# Modulo_Generico.net
KiCad netlist of a schematic drawn in Altium Designer
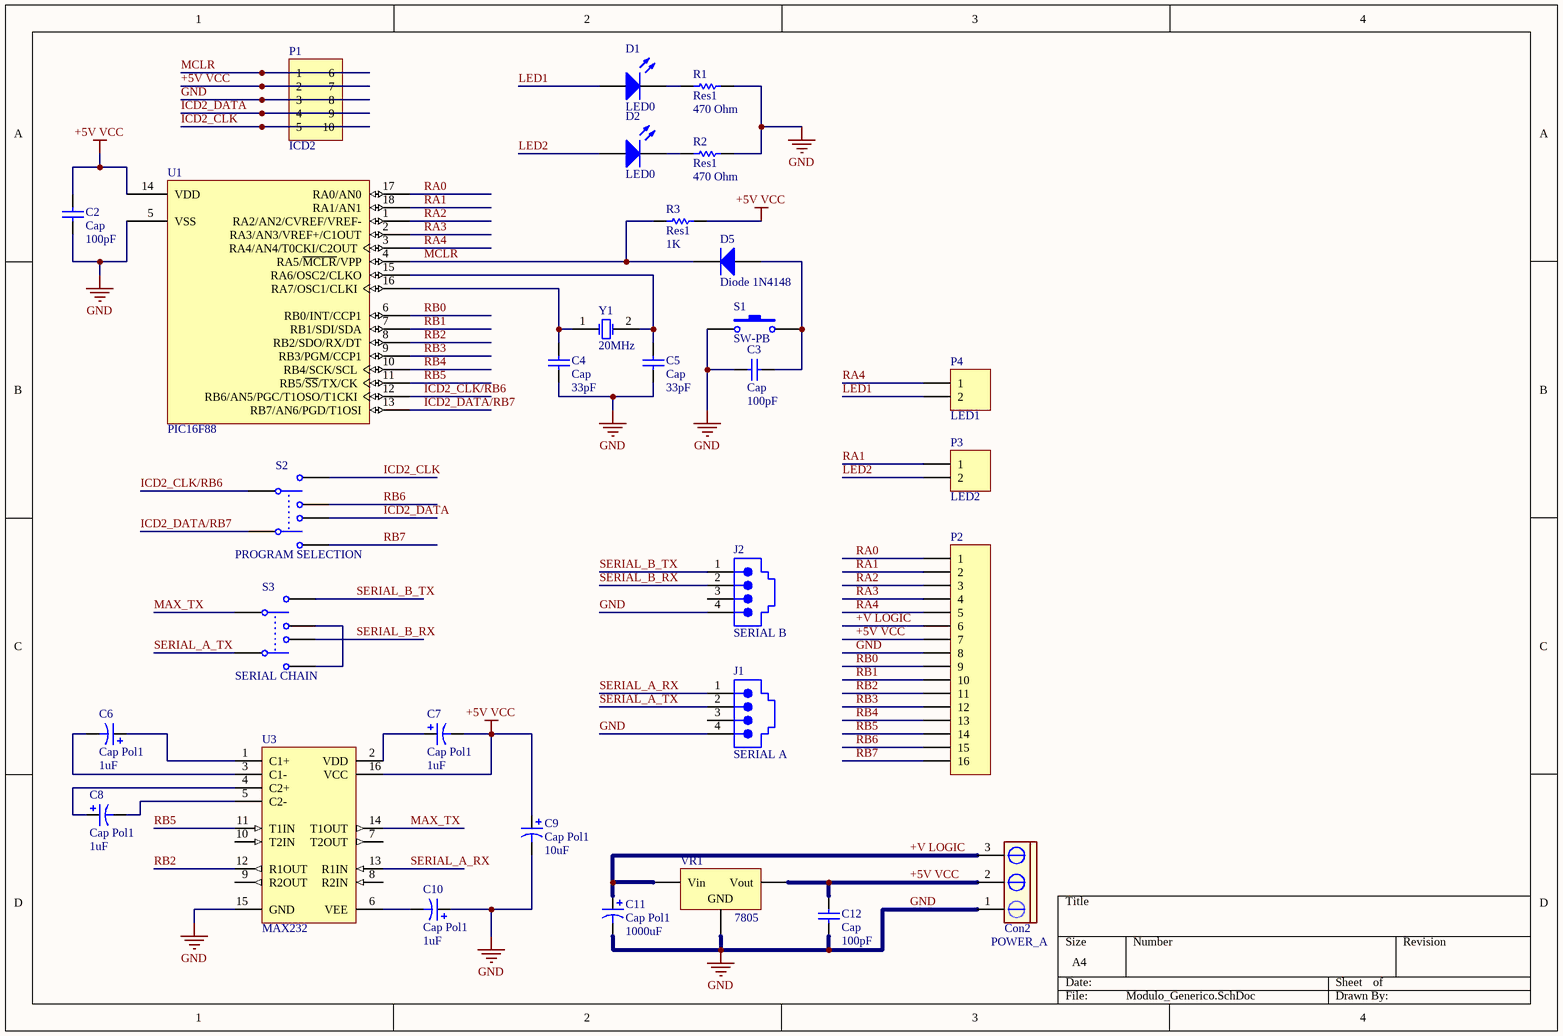
[diagram p0: Modulo_Generico.SchDoc]

(export (version "E")
  (design (tool "Eeschema 10.0.6"))
  (components
    (comp (ref "C2")
      (value "Cap")
      (footprint "CAPR2.54-5.1x3.2")
      (description "Capacitor")
      (fields (field (name "ALTIUM_VALUE") "100pF") (field (name "PUBLISHER") "Altium Limited"))
      (libsource (lib "Miscellaneous Devices") (part "Cap"))
    )
    (comp (ref "C3")
      (value "Cap")
      (footprint "CAPR2.54-5.1x3.2")
      (description "Capacitor")
      (fields (field (name "ALTIUM_VALUE") "100pF") (field (name "PUBLISHER") "Altium Limited"))
      (libsource (lib "Miscellaneous Devices") (part "Cap"))
    )
    (comp (ref "C4")
      (value "Cap")
      (footprint "CAPR2.54-5.1x3.2")
      (description "Capacitor")
      (fields (field (name "ALTIUM_VALUE") "33pF") (field (name "PUBLISHER") "Altium Limited"))
      (libsource (lib "Miscellaneous Devices") (part "Cap"))
    )
    (comp (ref "C5")
      (value "Cap")
      (footprint "CAPR2.54-5.1x3.2")
      (description "Capacitor")
      (fields (field (name "ALTIUM_VALUE") "33pF") (field (name "PUBLISHER") "Altium Limited"))
      (libsource (lib "Miscellaneous Devices") (part "Cap"))
    )
    (comp (ref "C6")
      (value "Cap Pol1")
      (footprint "CAPPR2-5x6.8")
      (description "Polarized Capacitor (Radial)")
      (fields (field (name "ALTIUM_VALUE") "1uF") (field (name "PUBLISHER") "Altium Limited"))
      (libsource (lib "Miscellaneous Devices") (part "Cap Pol1"))
    )
    (comp (ref "C7")
      (value "Cap Pol1")
      (footprint "CAPPR2-5x6.8")
      (description "Polarized Capacitor (Radial)")
      (fields (field (name "ALTIUM_VALUE") "1uF") (field (name "PUBLISHER") "Altium Limited"))
      (libsource (lib "Miscellaneous Devices") (part "Cap Pol1"))
    )
    (comp (ref "C8")
      (value "Cap Pol1")
      (footprint "CAPPR2-5x6.8")
      (description "Polarized Capacitor (Radial)")
      (fields (field (name "ALTIUM_VALUE") "1uF") (field (name "PUBLISHER") "Altium Limited"))
      (libsource (lib "Miscellaneous Devices") (part "Cap Pol1"))
    )
    (comp (ref "C9")
      (value "Cap Pol1")
      (footprint "CAPPR2-5x6.8")
      (description "Polarized Capacitor (Radial)")
      (fields (field (name "ALTIUM_VALUE") "10uF") (field (name "PUBLISHER") "Altium Limited"))
      (libsource (lib "Miscellaneous Devices") (part "Cap Pol1"))
    )
    (comp (ref "C10")
      (value "Cap Pol1")
      (footprint "CAPPR2-5x6.8")
      (description "Polarized Capacitor (Radial)")
      (fields (field (name "ALTIUM_VALUE") "1uF") (field (name "PUBLISHER") "Altium Limited"))
      (libsource (lib "Miscellaneous Devices") (part "Cap Pol1"))
    )
    (comp (ref "C11")
      (value "Cap Pol1")
      (footprint "RB5-10.5")
      (description "Polarized Capacitor (Radial)")
      (fields (field (name "ALTIUM_VALUE") "1000uF") (field (name "PUBLISHER") "Altium Limited"))
      (libsource (lib "Miscellaneous Devices") (part "Cap Pol1"))
    )
    (comp (ref "C12")
      (value "Cap")
      (footprint "CAPR2.54-5.1x3.2")
      (description "Capacitor")
      (fields (field (name "ALTIUM_VALUE") "100pF") (field (name "PUBLISHER") "Altium Limited"))
      (libsource (lib "Miscellaneous Devices") (part "Cap"))
    )
    (comp (ref "Con2")
      (value "POWER_A")
      (footprint "My_CN3")
      (description "Connector green screw")
      (libsource (lib "Protel_Library") (part "CON3 pin Green"))
    )
    (comp (ref "D1")
      (value "LED0")
      (footprint "LED-0")
      (description "Typical INFRARED GaAs LED")
      (fields (field (name "PUBLISHER") "Altium Limited"))
      (libsource (lib "Miscellaneous Devices") (part "LED0"))
    )
    (comp (ref "D2")
      (value "LED0")
      (footprint "LED-0")
      (description "Typical INFRARED GaAs LED")
      (fields (field (name "PUBLISHER") "Altium Limited"))
      (libsource (lib "Miscellaneous Devices") (part "LED0"))
    )
    (comp (ref "D5")
      (value "Diode 1N4148")
      (footprint "DIO7.1-3.9x1.9")
      (description "High Conductance Fast Diode")
      (fields (field (name "PUBLISHER") "Altium Limited"))
      (libsource (lib "Miscellaneous Devices") (part "Diode 1N4148"))
    )
    (comp (ref "J1")
      (value "SERIAL A")
      (footprint "15-43-6245")
      (description "Right Angle, Standard Profile, RJ45-Keyed, Flange Mount PCB Jack")
      (fields (field (name "PUBLISHER") "Altium Limited"))
      (libsource (lib "Molex Modular Jack Right Angle") (part "15-43-6245"))
    )
    (comp (ref "J2")
      (value "SERIAL B")
      (footprint "15-43-6245")
      (description "Right Angle, Standard Profile, RJ45-Keyed, Flange Mount PCB Jack")
      (fields (field (name "PUBLISHER") "Altium Limited"))
      (libsource (lib "Molex Modular Jack Right Angle") (part "15-43-6245"))
    )
    (comp (ref "P1")
      (value "ICD2")
      (footprint "HEADER10_5x2_B")
      (description "Header, 5-Pin, Dual row")
      (fields (field (name "PUBLISHER") "Altium Limited"))
      (libsource (lib "Miscellaneous Connectors") (part "Header 5X2A"))
    )
    (comp (ref "P2")
      (value "Header 16")
      (footprint "My_1X16")
      (description "Header, 16-Pin")
      (fields (field (name "PUBLISHER") "Altium Limited"))
      (libsource (lib "Protel_Library") (part "Header 16"))
    )
    (comp (ref "P3")
      (value "LED2")
      (footprint "HDR1X2")
      (description "Header, 2-Pin")
      (fields (field (name "PUBLISHER") "Altium Limited"))
      (libsource (lib "Miscellaneous Connectors") (part "Header 2"))
    )
    (comp (ref "P4")
      (value "LED1")
      (footprint "HDR1X2")
      (description "Header, 2-Pin")
      (fields (field (name "PUBLISHER") "Altium Limited"))
      (libsource (lib "Miscellaneous Connectors") (part "Header 2"))
    )
    (comp (ref "R1")
      (value "Res1")
      (footprint "AXIAL-0.3")
      (description "Resistor")
      (fields (field (name "ALTIUM_VALUE") "470 Ohm") (field (name "PUBLISHER") "Altium Limited"))
      (libsource (lib "Miscellaneous Devices") (part "Res1"))
    )
    (comp (ref "R2")
      (value "Res1")
      (footprint "AXIAL-0.3")
      (description "Resistor")
      (fields (field (name "ALTIUM_VALUE") "470 Ohm") (field (name "PUBLISHER") "Altium Limited"))
      (libsource (lib "Miscellaneous Devices") (part "Res1"))
    )
    (comp (ref "R3")
      (value "Res1")
      (footprint "AXIAL-0.3")
      (description "Resistor")
      (fields (field (name "ALTIUM_VALUE") "1K") (field (name "PUBLISHER") "Altium Limited"))
      (libsource (lib "Miscellaneous Devices") (part "Res1"))
    )
    (comp (ref "S1")
      (value "SW-PB")
      (footprint "TS-063")
      (description "Switch")
      (fields (field (name "PUBLISHER") "Altium Limited"))
      (libsource (lib "Miscellaneous Devices") (part "SW-PB"))
    )
    (comp (ref "S2")
      (value "PROGRAM SELECTION")
      (footprint "LD-202mini")
      (description "Double-Pole, Double-Throw Switch")
      (fields (field (name "PUBLISHER") "Altium Limited"))
      (libsource (lib "Miscellaneous Devices") (part "SW-DPDT"))
    )
    (comp (ref "S3")
      (value "SERIAL CHAIN")
      (footprint "LD-202mini")
      (description "Double-Pole, Double-Throw Switch")
      (fields (field (name "PUBLISHER") "Altium Limited"))
      (libsource (lib "Miscellaneous Devices") (part "SW-DPDT"))
    )
    (comp (ref "U1")
      (value "PIC16F88")
      (footprint "PDIP300-P18")
      (fields (field (name "PUBLISHER") "Altium Limited"))
      (libsource (lib "Microchip Microcontroller 8-Bit PIC16") (part "PIC16F88-E/P"))
    )
    (comp (ref "U3")
      (value "MAX232")
      (footprint "PE16A")
      (description "+5V Powered, Multi-Channel RS-232 Driver/Receiver")
      (fields (field (name "PUBLISHER") "Altium Limited"))
      (libsource (lib "Maxim Communication Transceiver") (part "MAX232ACPE"))
    )
    (comp (ref "VR1")
      (value "7805")
      (footprint "My_TO-220")
      (description "Voltage Regulator")
      (fields (field (name "PUBLISHER") "Altium Limited"))
      (libsource (lib "Miscellaneous Devices") (part "Volt Reg"))
    )
    (comp (ref "Y1")
      (value "20MHz")
      (footprint "My_Crystal")
      (description "Crystal Oscillator")
      (fields (field (name "PUBLISHER") "Altium Limited"))
      (libsource (lib "Miscellaneous Devices") (part "XTAL"))
    )
  )
  (nets
    (net (code "1") (name "+5V VCC") (class "Default")
      (node (ref "C12") (pin "2") (pinfunction "2_2") (pintype "passive"))
      (node (ref "C2") (pin "2") (pinfunction "2_2") (pintype "passive"))
      (node (ref "C7") (pin "2") (pinfunction "2_2") (pintype "passive"))
      (node (ref "C9") (pin "1") (pinfunction "1_1") (pintype "passive"))
      (node (ref "Con2") (pin "2") (pinfunction "2_2") (pintype "passive"))
      (node (ref "P1") (pin "2") (pinfunction "2_2") (pintype "passive"))
      (node (ref "P1") (pin "7") (pinfunction "7_7") (pintype "passive"))
      (node (ref "P2") (pin "7") (pinfunction "7_7") (pintype "passive"))
      (node (ref "R3") (pin "2") (pinfunction "2_2") (pintype "passive"))
      (node (ref "U1") (pin "14") (pinfunction "VDD_14") (pintype "power_in"))
      (node (ref "U3") (pin "16") (pinfunction "VCC_16") (pintype "power_in"))
      (node (ref "VR1") (pin "3") (pinfunction "Vout_3") (pintype "passive"))
    )
    (net (code "2") (name "/+V LOGIC") (class "Default")
      (node (ref "C11") (pin "1") (pinfunction "1_1") (pintype "passive"))
      (node (ref "Con2") (pin "3") (pinfunction "3_3") (pintype "passive"))
      (node (ref "P2") (pin "6") (pinfunction "6_6") (pintype "passive"))
      (node (ref "VR1") (pin "1") (pinfunction "Vin_1") (pintype "passive"))
    )
    (net (code "3") (name "/ICD2_CLK") (class "Default")
      (node (ref "P1") (pin "10") (pinfunction "10_10") (pintype "passive"))
      (node (ref "P1") (pin "5") (pinfunction "5_5") (pintype "passive"))
      (node (ref "S2") (pin "2") (pinfunction "2_2") (pintype "passive"))
    )
    (net (code "4") (name "/ICD2_CLK{slash}RB6") (class "Default")
      (node (ref "S2") (pin "1") (pinfunction "1_1") (pintype "passive"))
      (node (ref "U1") (pin "12") (pinfunction "RB6/AN5/PGC/T1OSO/T1CKI_12") (pintype "bidirectional"))
    )
    (net (code "5") (name "/ICD2_DATA") (class "Default")
      (node (ref "P1") (pin "4") (pinfunction "4_4") (pintype "passive"))
      (node (ref "P1") (pin "9") (pinfunction "9_9") (pintype "passive"))
      (node (ref "S2") (pin "5") (pinfunction "5_5") (pintype "passive"))
    )
    (net (code "6") (name "/ICD2_DATA{slash}RB7") (class "Default")
      (node (ref "S2") (pin "4") (pinfunction "4_4") (pintype "passive"))
      (node (ref "U1") (pin "13") (pinfunction "RB7/AN6/PGD/T1OSI_13") (pintype "bidirectional"))
    )
    (net (code "7") (name "/LED1") (class "Default")
      (node (ref "D1") (pin "1") (pinfunction "A_1") (pintype "passive"))
      (node (ref "P4") (pin "2") (pinfunction "2_2") (pintype "passive"))
    )
    (net (code "8") (name "/LED2") (class "Default")
      (node (ref "D2") (pin "1") (pinfunction "A_1") (pintype "passive"))
      (node (ref "P3") (pin "2") (pinfunction "2_2") (pintype "passive"))
    )
    (net (code "9") (name "/MAX_TX") (class "Default")
      (node (ref "S3") (pin "1") (pinfunction "1_1") (pintype "passive"))
      (node (ref "U3") (pin "14") (pinfunction "T1OUT_14") (pintype "output"))
    )
    (net (code "10") (name "/MCLR") (class "Default")
      (node (ref "D5") (pin "2") (pinfunction "K_2") (pintype "passive"))
      (node (ref "P1") (pin "1") (pinfunction "1_1") (pintype "passive"))
      (node (ref "P1") (pin "6") (pinfunction "6_6") (pintype "passive"))
      (node (ref "R3") (pin "1") (pinfunction "1_1") (pintype "passive"))
      (node (ref "U1") (pin "4") (pinfunction "RA5/~{MCLR}/VPP_4") (pintype "bidirectional"))
    )
    (net (code "11") (name "/RA0") (class "Default")
      (node (ref "P2") (pin "1") (pinfunction "1_1") (pintype "passive"))
      (node (ref "U1") (pin "17") (pinfunction "RA0/AN0_17") (pintype "bidirectional"))
    )
    (net (code "12") (name "/RA1") (class "Default")
      (node (ref "P2") (pin "2") (pinfunction "2_2") (pintype "passive"))
      (node (ref "P3") (pin "1") (pinfunction "1_1") (pintype "passive"))
      (node (ref "U1") (pin "18") (pinfunction "RA1/AN1_18") (pintype "bidirectional"))
    )
    (net (code "13") (name "/RA2") (class "Default")
      (node (ref "P2") (pin "3") (pinfunction "3_3") (pintype "passive"))
      (node (ref "U1") (pin "1") (pinfunction "RA2/AN2/CVREF/VREF-_1") (pintype "bidirectional"))
    )
    (net (code "14") (name "/RA3") (class "Default")
      (node (ref "P2") (pin "4") (pinfunction "4_4") (pintype "passive"))
      (node (ref "U1") (pin "2") (pinfunction "RA3/AN3/VREF+/C1OUT_2") (pintype "bidirectional"))
    )
    (net (code "15") (name "/RA4") (class "Default")
      (node (ref "P2") (pin "5") (pinfunction "5_5") (pintype "passive"))
      (node (ref "P4") (pin "1") (pinfunction "1_1") (pintype "passive"))
      (node (ref "U1") (pin "3") (pinfunction "RA4/AN4/T0CKI/C2OUT_3") (pintype "bidirectional"))
    )
    (net (code "16") (name "/RB0") (class "Default")
      (node (ref "P2") (pin "9") (pinfunction "9_9") (pintype "passive"))
      (node (ref "U1") (pin "6") (pinfunction "RB0/INT/CCP1_6") (pintype "bidirectional"))
    )
    (net (code "17") (name "/RB1") (class "Default")
      (node (ref "P2") (pin "10") (pinfunction "10_10") (pintype "passive"))
      (node (ref "U1") (pin "7") (pinfunction "RB1/SDI/SDA_7") (pintype "bidirectional"))
    )
    (net (code "18") (name "/RB2") (class "Default")
      (node (ref "P2") (pin "11") (pinfunction "11_11") (pintype "passive"))
      (node (ref "U1") (pin "8") (pinfunction "RB2/SDO/RX/DT_8") (pintype "bidirectional"))
      (node (ref "U3") (pin "12") (pinfunction "R1OUT_12") (pintype "output"))
    )
    (net (code "19") (name "/RB3") (class "Default")
      (node (ref "P2") (pin "12") (pinfunction "12_12") (pintype "passive"))
      (node (ref "U1") (pin "9") (pinfunction "RB3/PGM/CCP1_9") (pintype "bidirectional"))
    )
    (net (code "20") (name "/RB4") (class "Default")
      (node (ref "P2") (pin "13") (pinfunction "13_13") (pintype "passive"))
      (node (ref "U1") (pin "10") (pinfunction "RB4/SCK/SCL_10") (pintype "bidirectional"))
    )
    (net (code "21") (name "/RB5") (class "Default")
      (node (ref "P2") (pin "14") (pinfunction "14_14") (pintype "passive"))
      (node (ref "U1") (pin "11") (pinfunction "RB5/~{SS}/TX/CK_11") (pintype "bidirectional"))
      (node (ref "U3") (pin "11") (pinfunction "T1IN_11") (pintype "input"))
    )
    (net (code "22") (name "/RB6") (class "Default")
      (node (ref "P2") (pin "15") (pinfunction "15_15") (pintype "passive"))
      (node (ref "S2") (pin "3") (pinfunction "3_3") (pintype "passive"))
    )
    (net (code "23") (name "/RB7") (class "Default")
      (node (ref "P2") (pin "16") (pinfunction "16_16") (pintype "passive"))
      (node (ref "S2") (pin "6") (pinfunction "6_6") (pintype "passive"))
    )
    (net (code "24") (name "/SERIAL_A_RX") (class "Default")
      (node (ref "J1") (pin "1") (pinfunction "1_1") (pintype "passive"))
      (node (ref "U3") (pin "13") (pinfunction "R1IN_13") (pintype "input"))
    )
    (net (code "25") (name "/SERIAL_A_TX") (class "Default")
      (node (ref "J1") (pin "2") (pinfunction "2_2") (pintype "passive"))
      (node (ref "S3") (pin "4") (pinfunction "4_4") (pintype "passive"))
    )
    (net (code "26") (name "/SERIAL_B_RX") (class "Default")
      (node (ref "J2") (pin "2") (pinfunction "2_2") (pintype "passive"))
      (node (ref "S3") (pin "5") (pinfunction "5_5") (pintype "passive"))
    )
    (net (code "27") (name "/SERIAL_B_TX") (class "Default")
      (node (ref "J2") (pin "1") (pinfunction "1_1") (pintype "passive"))
      (node (ref "S3") (pin "2") (pinfunction "2_2") (pintype "passive"))
    )
    (net (code "28") (name "GND") (class "Default")
      (node (ref "C10") (pin "1") (pinfunction "1_1") (pintype "passive"))
      (node (ref "C11") (pin "2") (pinfunction "2_2") (pintype "passive"))
      (node (ref "C12") (pin "1") (pinfunction "1_1") (pintype "passive"))
      (node (ref "C2") (pin "1") (pinfunction "1_1") (pintype "passive"))
      (node (ref "C3") (pin "1") (pinfunction "1_1") (pintype "passive"))
      (node (ref "C4") (pin "1") (pinfunction "1_1") (pintype "passive"))
      (node (ref "C5") (pin "1") (pinfunction "1_1") (pintype "passive"))
      (node (ref "C9") (pin "2") (pinfunction "2_2") (pintype "passive"))
      (node (ref "Con2") (pin "1") (pinfunction "1_1") (pintype "passive"))
      (node (ref "J1") (pin "4") (pinfunction "4_4") (pintype "passive"))
      (node (ref "J2") (pin "4") (pinfunction "4_4") (pintype "passive"))
      (node (ref "P1") (pin "3") (pinfunction "3_3") (pintype "passive"))
      (node (ref "P1") (pin "8") (pinfunction "8_8") (pintype "passive"))
      (node (ref "P2") (pin "8") (pinfunction "8_8") (pintype "passive"))
      (node (ref "R1") (pin "2") (pinfunction "2_2") (pintype "passive"))
      (node (ref "R2") (pin "2") (pinfunction "2_2") (pintype "passive"))
      (node (ref "S1") (pin "1") (pinfunction "1_1") (pintype "passive"))
      (node (ref "U1") (pin "5") (pinfunction "VSS_5") (pintype "power_in"))
      (node (ref "U3") (pin "15") (pinfunction "GND_15") (pintype "power_in"))
      (node (ref "VR1") (pin "2") (pinfunction "GND_2") (pintype "passive"))
    )
    (net (code "29") (name "Net-(D1-K)") (class "Default")
      (node (ref "D1") (pin "2") (pinfunction "K_2") (pintype "passive"))
      (node (ref "R1") (pin "1") (pinfunction "1_1") (pintype "passive"))
    )
    (net (code "30") (name "Net-(D2-K)") (class "Default")
      (node (ref "D2") (pin "2") (pinfunction "K_2") (pintype "passive"))
      (node (ref "R2") (pin "1") (pinfunction "1_1") (pintype "passive"))
    )
    (net (code "31") (name "Net-(D5-A)") (class "Default")
      (node (ref "C3") (pin "2") (pinfunction "2_2") (pintype "passive"))
      (node (ref "D5") (pin "1") (pinfunction "A_1") (pintype "passive"))
      (node (ref "S1") (pin "2") (pinfunction "2_2") (pintype "passive"))
    )
    (net (code "32") (name "Net-(S3-Pad3)") (class "Default")
      (node (ref "S3") (pin "3") (pinfunction "3_3") (pintype "passive"))
      (node (ref "S3") (pin "6") (pinfunction "6_6") (pintype "passive"))
    )
    (net (code "33") (name "Net-(U1-RA6{slash}OSC2{slash}CLKO)") (class "Default")
      (node (ref "C5") (pin "2") (pinfunction "2_2") (pintype "passive"))
      (node (ref "U1") (pin "15") (pinfunction "RA6/OSC2/CLKO_15") (pintype "bidirectional"))
      (node (ref "Y1") (pin "2") (pinfunction "OSC2_2") (pintype "passive"))
    )
    (net (code "34") (name "Net-(U1-RA7{slash}OSC1{slash}CLKI)") (class "Default")
      (node (ref "C4") (pin "2") (pinfunction "2_2") (pintype "passive"))
      (node (ref "U1") (pin "16") (pinfunction "RA7/OSC1/CLKI_16") (pintype "bidirectional"))
      (node (ref "Y1") (pin "1") (pinfunction "OSC1_1") (pintype "passive"))
    )
    (net (code "35") (name "Net-(U3-C1+)") (class "Default")
      (node (ref "C6") (pin "1") (pinfunction "1_1") (pintype "passive"))
      (node (ref "U3") (pin "1") (pinfunction "C1+_1") (pintype "passive"))
    )
    (net (code "36") (name "Net-(U3-C1-)") (class "Default")
      (node (ref "C6") (pin "2") (pinfunction "2_2") (pintype "passive"))
      (node (ref "U3") (pin "3") (pinfunction "C1-_3") (pintype "passive"))
    )
    (net (code "37") (name "Net-(U3-C2+)") (class "Default")
      (node (ref "C8") (pin "1") (pinfunction "1_1") (pintype "passive"))
      (node (ref "U3") (pin "4") (pinfunction "C2+_4") (pintype "passive"))
    )
    (net (code "38") (name "Net-(U3-C2-)") (class "Default")
      (node (ref "C8") (pin "2") (pinfunction "2_2") (pintype "passive"))
      (node (ref "U3") (pin "5") (pinfunction "C2-_5") (pintype "passive"))
    )
    (net (code "39") (name "Net-(U3-VDD)") (class "Default")
      (node (ref "C7") (pin "1") (pinfunction "1_1") (pintype "passive"))
      (node (ref "U3") (pin "2") (pinfunction "VDD_2") (pintype "power_in"))
    )
    (net (code "40") (name "Net-(U3-VEE)") (class "Default")
      (node (ref "C10") (pin "2") (pinfunction "2_2") (pintype "passive"))
      (node (ref "U3") (pin "6") (pinfunction "VEE_6") (pintype "power_in"))
    )
    (net (code "41") (name "unconnected-(J1-Pad3)") (class "Default")
      (node (ref "J1") (pin "3") (pinfunction "3_3") (pintype "passive"))
    )
    (net (code "42") (name "unconnected-(J2-Pad3)") (class "Default")
      (node (ref "J2") (pin "3") (pinfunction "3_3") (pintype "passive"))
    )
    (net (code "43") (name "unconnected-(U3-R2IN-Pad8)") (class "Default")
      (node (ref "U3") (pin "8") (pinfunction "R2IN_8") (pintype "input"))
    )
    (net (code "44") (name "unconnected-(U3-R2OUT-Pad9)") (class "Default")
      (node (ref "U3") (pin "9") (pinfunction "R2OUT_9") (pintype "output"))
    )
    (net (code "45") (name "unconnected-(U3-T2IN-Pad10)") (class "Default")
      (node (ref "U3") (pin "10") (pinfunction "T2IN_10") (pintype "input"))
    )
    (net (code "46") (name "unconnected-(U3-T2OUT-Pad7)") (class "Default")
      (node (ref "U3") (pin "7") (pinfunction "T2OUT_7") (pintype "output"))
    )
  )
)
